# sensor_board_v0_53.net
KiCad netlist of a schematic drawn in EAGLE
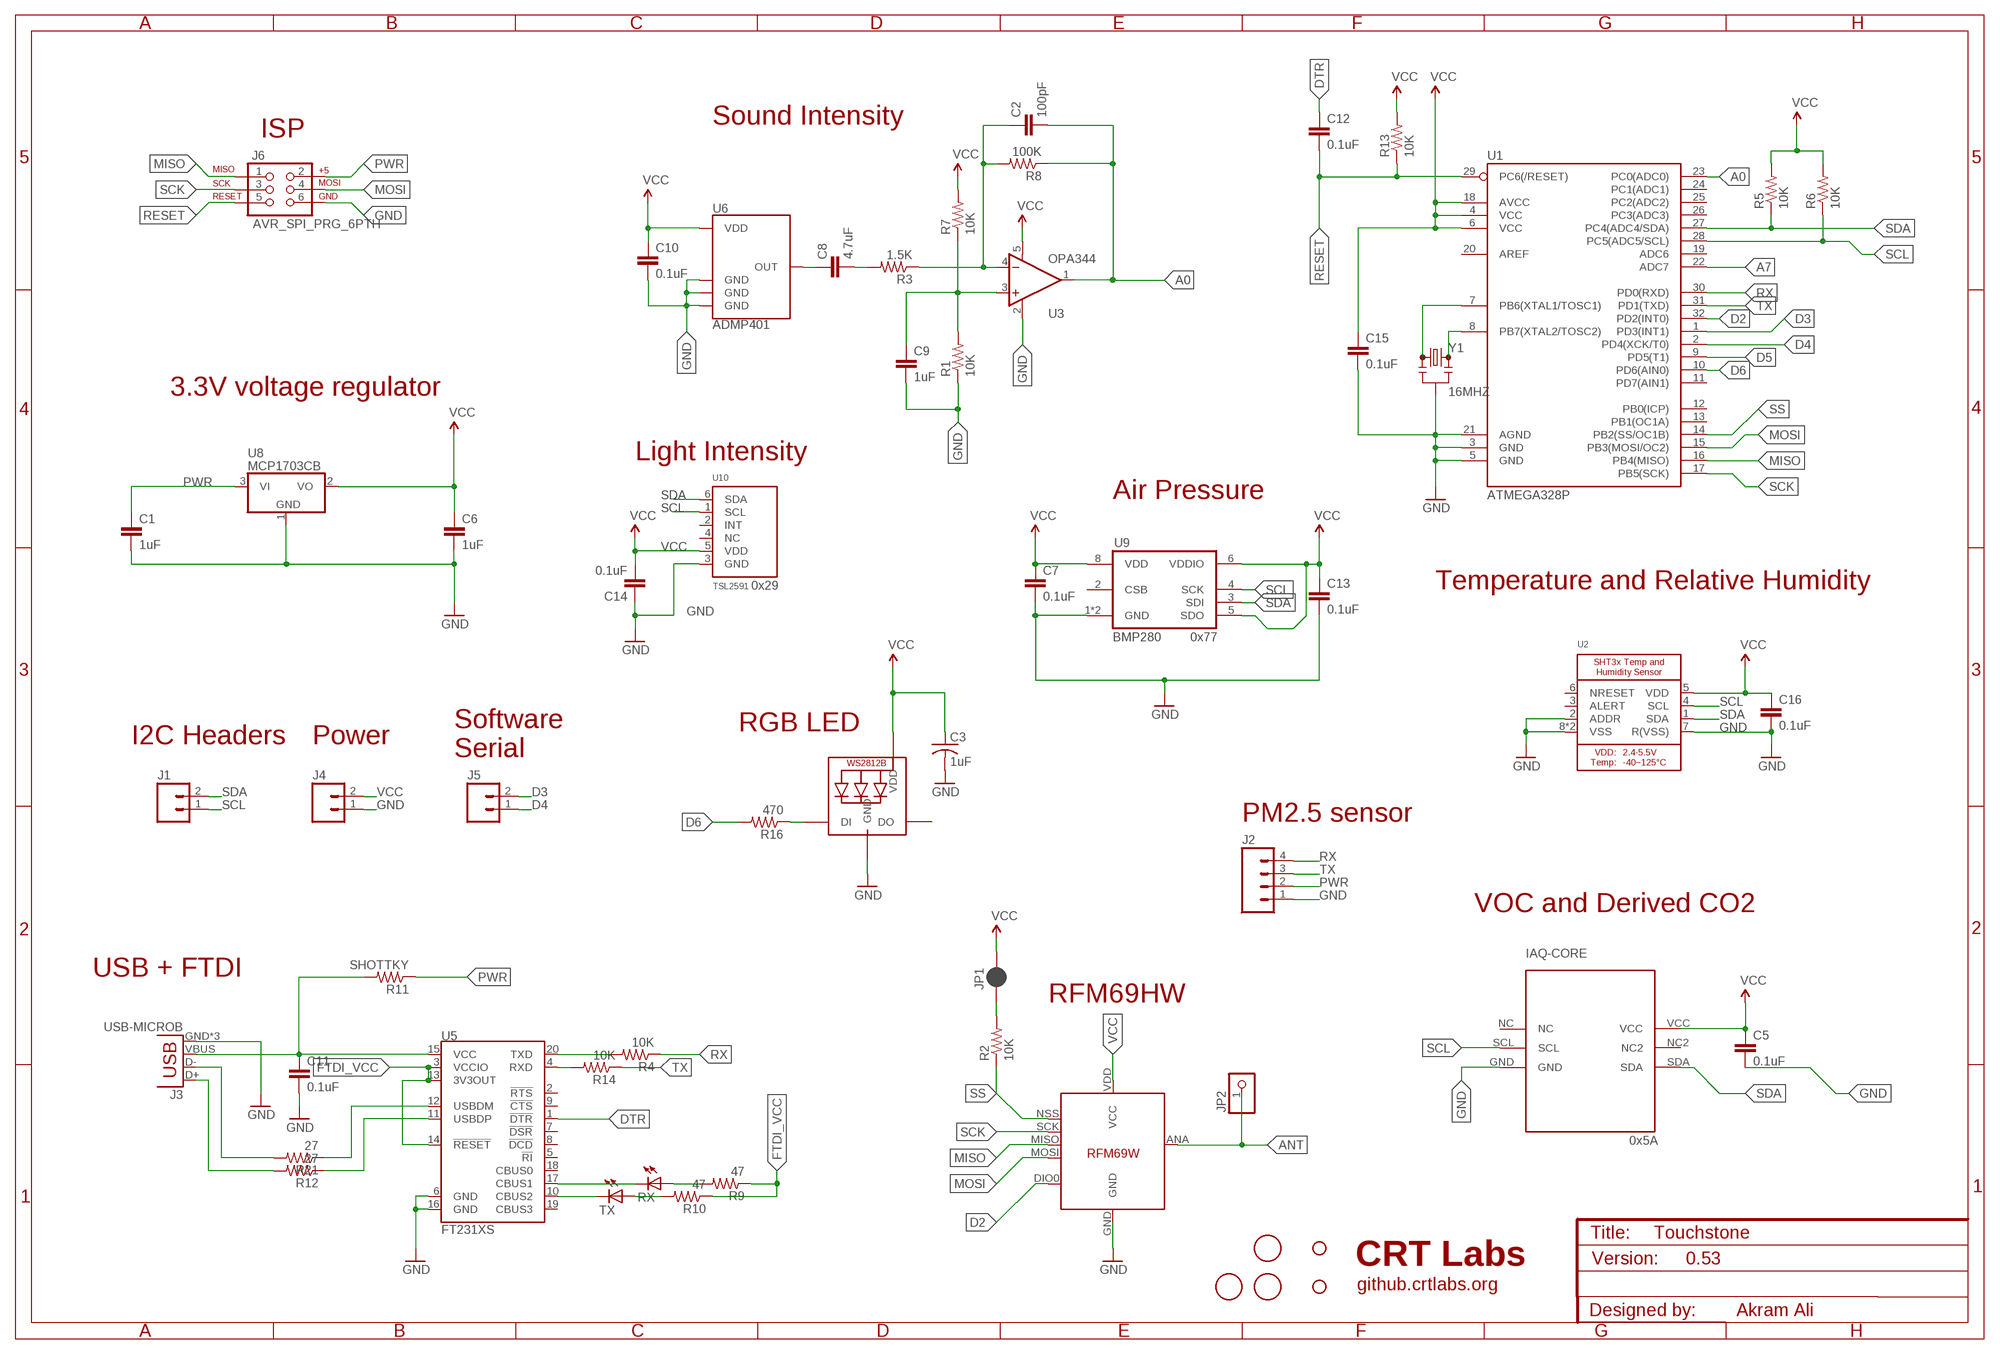
[diagram p0: schematic, sheet 1]

(export (version "E")
  (design (tool "Eeschema 10.0.6"))
  (components
    (comp (ref "C1")
      (value "1uF")
      (footprint "eagle-import:0805")
      (fields (field (name "MPN") "CC0805ZRY5V8BB105"))
      (libsource (lib "eagle-import") (part "CAP0805"))
    )
    (comp (ref "C2")
      (value "100pF")
      (footprint "eagle-import:0805")
      (fields (field (name "MPN") "CC0805JRNPOABN101"))
      (libsource (lib "eagle-import") (part "CAP0805"))
    )
    (comp (ref "C3")
      (value "1uF")
      (footprint "eagle-import:C0603K")
      (fields (field (name "MPN") "CC0805ZRY5V8BB105"))
      (libsource (lib "eagle-import") (part "C-USC0603K"))
    )
    (comp (ref "C5")
      (value "0.1uF")
      (footprint "eagle-import:0805")
      (fields (field (name "MPN") "CC0805KRX7R9BB104"))
      (libsource (lib "eagle-import") (part "SparkFun-Passives_CAP0805"))
    )
    (comp (ref "C6")
      (value "1uF")
      (footprint "eagle-import:0805")
      (fields (field (name "MPN") "CC0805ZRY5V8BB105"))
      (libsource (lib "eagle-import") (part "CAP0805"))
    )
    (comp (ref "C7")
      (value "0.1uF")
      (footprint "eagle-import:0805")
      (fields (field (name "MPN") "CC0805KRX7R9BB104"))
      (libsource (lib "eagle-import") (part "SparkFun-Passives_CAP0805"))
    )
    (comp (ref "C8")
      (value "4.7uF")
      (footprint "eagle-import:0805")
      (fields (field (name "MPN") "CC0805KKX7R6BB475"))
      (libsource (lib "eagle-import") (part "CAP0805"))
    )
    (comp (ref "C9")
      (value "1uF")
      (footprint "eagle-import:0805")
      (fields (field (name "MPN") "CC0805ZRY5V8BB105"))
      (libsource (lib "eagle-import") (part "CAP0805"))
    )
    (comp (ref "C10")
      (value "0.1uF")
      (footprint "eagle-import:0805")
      (fields (field (name "MPN") "CC0805KRX7R9BB104"))
      (libsource (lib "eagle-import") (part "CAP0805"))
    )
    (comp (ref "C11")
      (value "0.1uF")
      (footprint "eagle-import:0805")
      (fields (field (name "MPN") "CC0805KRX7R9BB104"))
      (libsource (lib "eagle-import") (part "CAP0805"))
    )
    (comp (ref "C12")
      (value "0.1uF")
      (footprint "eagle-import:0805")
      (fields (field (name "MPN") "CC0805KRX7R9BB104"))
      (libsource (lib "eagle-import") (part "SparkFun-Passives_CAP0805"))
    )
    (comp (ref "C13")
      (value "0.1uF")
      (footprint "eagle-import:0805")
      (fields (field (name "MPN") "CC0805KRX7R9BB104"))
      (libsource (lib "eagle-import") (part "SparkFun-Passives_CAP0805"))
    )
    (comp (ref "C14")
      (value "0.1uF")
      (footprint "eagle-import:0805")
      (fields (field (name "MPN") "CC0805KRX7R9BB104"))
      (libsource (lib "eagle-import") (part "SparkFun-Passives_CAP0805"))
    )
    (comp (ref "C15")
      (value "0.1uF")
      (footprint "eagle-import:0805")
      (fields (field (name "MPN") "CC0805KRX7R9BB104"))
      (libsource (lib "eagle-import") (part "SparkFun-Passives_CAP0805"))
    )
    (comp (ref "C16")
      (value "0.1uF")
      (footprint "eagle-import:0805")
      (fields (field (name "MPN") "CC0805KRX7R9BB104"))
      (libsource (lib "eagle-import") (part "SparkFun-Passives_CAP0805"))
    )
    (comp (ref "H1")
      (value "STAND-OFF")
      (footprint "eagle-import:STAND-OFF")
      (libsource (lib "eagle-import") (part "STAND-OFF"))
    )
    (comp (ref "H2")
      (value "STAND-OFF")
      (footprint "eagle-import:STAND-OFF")
      (libsource (lib "eagle-import") (part "STAND-OFF"))
    )
    (comp (ref "IAQ-CORE")
      (value "IAQ-CORE")
      (footprint "eagle-import:IAQ-CORE")
      (fields (field (name "MPN") "IAQ-CORE C"))
      (libsource (lib "eagle-import") (part "IAQ-CORE"))
    )
    (comp (ref "J1")
      (value "M02PTH")
      (footprint "eagle-import:1X02")
      (libsource (lib "eagle-import") (part "M02PTH"))
    )
    (comp (ref "J2")
      (value "M04PTH")
      (footprint "eagle-import:1X04")
      (libsource (lib "eagle-import") (part "M04PTH"))
    )
    (comp (ref "J3")
      (value "USB-MICROB")
      (footprint "eagle-import:USB-MICROB")
      (fields (field (name "MPN") "47346-0001"))
      (libsource (lib "eagle-import") (part "USB-MICROB"))
    )
    (comp (ref "J4")
      (value "M02PTH")
      (footprint "eagle-import:1X02")
      (libsource (lib "eagle-import") (part "M02PTH"))
    )
    (comp (ref "J5")
      (value "M02PTH")
      (footprint "eagle-import:1X02")
      (libsource (lib "eagle-import") (part "M02PTH"))
    )
    (comp (ref "J6")
      (value "AVR_SPI_PRG_6PTH")
      (footprint "eagle-import:2X3")
      (libsource (lib "eagle-import") (part "AVR_SPI_PRG_6PTH"))
    )
    (comp (ref "JP1")
      (value "JUMPER-PAD-2-NC_BY_PASTEFULL-BOX-SILK")
      (footprint "eagle-import:PAD-JUMPER-2-NC_BY_PASTE_YES_SILK_FULL_BOX")
      (libsource (lib "eagle-import") (part "JUMPER-PAD-2-NC_BY_PASTEFULL-BOX-SILK"))
    )
    (comp (ref "JP2")
      (value "PINHD-1X1")
      (footprint "eagle-import:1X01")
      (libsource (lib "eagle-import") (part "PINHD-1X1"))
    )
    (comp (ref "LED1")
      (value "WS2812B3535")
      (footprint "eagle-import:LED3535")
      (fields (field (name "MPN") "SK6812 mini"))
      (libsource (lib "eagle-import") (part "WS2812B3535"))
    )
    (comp (ref "R1")
      (value "10K")
      (footprint "eagle-import:0805")
      (fields (field (name "MPN") "RC0805FR-0710KL"))
      (libsource (lib "eagle-import") (part "RESISTOR0805-RES"))
    )
    (comp (ref "R2")
      (value "10K")
      (footprint "eagle-import:0805")
      (fields (field (name "MPN") "RC0805FR-0710KL"))
      (libsource (lib "eagle-import") (part "RESISTOR0805-RES"))
    )
    (comp (ref "R3")
      (value "1.5K")
      (footprint "eagle-import:0805")
      (fields (field (name "MPN") "RC0805FR-071K5L "))
      (libsource (lib "eagle-import") (part "RESISTOR0805-RES"))
    )
    (comp (ref "R4")
      (value "10K")
      (footprint "eagle-import:0805")
      (fields (field (name "MPN") "RC0805FR-0710KL"))
      (libsource (lib "eagle-import") (part "RESISTOR0805-RES"))
    )
    (comp (ref "R5")
      (value "10K")
      (footprint "eagle-import:0805")
      (fields (field (name "MPN") "RC0805FR-0710KL"))
      (libsource (lib "eagle-import") (part "SparkFun-Resistors_RESISTOR0805-RES"))
    )
    (comp (ref "R6")
      (value "10K")
      (footprint "eagle-import:0805")
      (fields (field (name "MPN") "RC0805FR-0710KL"))
      (libsource (lib "eagle-import") (part "SparkFun-Resistors_RESISTOR0805-RES"))
    )
    (comp (ref "R7")
      (value "10K")
      (footprint "eagle-import:0805")
      (fields (field (name "MPN") "RC0805FR-0710KL"))
      (libsource (lib "eagle-import") (part "RESISTOR0805-RES"))
    )
    (comp (ref "R8")
      (value "100K")
      (footprint "eagle-import:0805")
      (fields (field (name "MPN") "RC0805FR-07100KL "))
      (libsource (lib "eagle-import") (part "RESISTOR0805-RES"))
    )
    (comp (ref "R9")
      (value "47")
      (footprint "eagle-import:0805")
      (fields (field (name "MPN") "RC0805FR-0747RL "))
      (libsource (lib "eagle-import") (part "RESISTOR0805-RES"))
    )
    (comp (ref "R10")
      (value "47")
      (footprint "eagle-import:0805")
      (fields (field (name "MPN") "RC0805FR-0747RL "))
      (libsource (lib "eagle-import") (part "RESISTOR0805-RES"))
    )
    (comp (ref "R11")
      (value "SHOTTKY")
      (footprint "eagle-import:0805")
      (fields (field (name "MPN") "SD0805S040S0R5"))
      (libsource (lib "eagle-import") (part "RESISTOR0805-RES"))
    )
    (comp (ref "R12")
      (value "27")
      (footprint "eagle-import:0805")
      (fields (field (name "MPN") "RC0805FR-0727RL "))
      (libsource (lib "eagle-import") (part "RESISTOR0805-RES"))
    )
    (comp (ref "R13")
      (value "10K")
      (footprint "eagle-import:0805")
      (fields (field (name "MPN") "RC0805FR-0710KL"))
      (libsource (lib "eagle-import") (part "RESISTOR0805-RES"))
    )
    (comp (ref "R14")
      (value "10K")
      (footprint "eagle-import:0805")
      (fields (field (name "MPN") "RC0805FR-0710KL"))
      (libsource (lib "eagle-import") (part "RESISTOR0805-RES"))
    )
    (comp (ref "R16")
      (value "470")
      (footprint "eagle-import:R0603")
      (fields (field (name "MPN") "RC0805FR-07470RL "))
      (libsource (lib "eagle-import") (part "R-US_R0603"))
    )
    (comp (ref "R21")
      (value "27")
      (footprint "eagle-import:0805")
      (fields (field (name "MPN") "RC0805FR-0727RL "))
      (libsource (lib "eagle-import") (part "RESISTOR0805-RES"))
    )
    (comp (ref "RX")
      (value "LEDCHIPLED_0805")
      (footprint "eagle-import:CHIPLED_0805")
      (fields (field (name "MPN") "LG R971-KN-1"))
      (libsource (lib "eagle-import") (part "LEDCHIPLED_0805"))
    )
    (comp (ref "TX")
      (value "LEDCHIPLED_0805")
      (footprint "eagle-import:CHIPLED_0805")
      (fields (field (name "MPN") "LG R971-KN-1"))
      (libsource (lib "eagle-import") (part "LEDCHIPLED_0805"))
    )
    (comp (ref "U$1")
      (value "FIDUCIAL")
      (footprint "eagle-import:FIDUCIAL_1MM")
      (libsource (lib "eagle-import") (part "FIDUCIAL"))
    )
    (comp (ref "U$2")
      (value "FIDUCIAL")
      (footprint "eagle-import:FIDUCIAL_1MM")
      (libsource (lib "eagle-import") (part "FIDUCIAL"))
    )
    (comp (ref "U$3")
      (value "FIDUCIAL")
      (footprint "eagle-import:FIDUCIAL_1MM")
      (libsource (lib "eagle-import") (part "FIDUCIAL"))
    )
    (comp (ref "U1")
      (value "ATMEGA328P")
      (footprint "eagle-import:TQFP32-08")
      (fields (field (name "MPN") "ATMEGA328PB-AU"))
      (libsource (lib "eagle-import") (part "ATMEGA328P_TQFP"))
    )
    (comp (ref "U2")
      (value "SHT3X")
      (footprint "eagle-import:SHT3X")
      (fields (field (name "MPN") "SHT35-DIS-B"))
      (libsource (lib "eagle-import") (part "SHT3X"))
    )
    (comp (ref "U3")
      (value "OPA344")
      (footprint "eagle-import:SOT23-5")
      (fields (field (name "MPN") "OPA344NA/3K"))
      (libsource (lib "eagle-import") (part "OPA344"))
    )
    (comp (ref "U4")
      (value "RFM69HW")
      (footprint "eagle-import:LOWPOWERLAB_RFM69W-MINPADS")
      (libsource (lib "eagle-import") (part "LOWPOWERLAB_RFM69"))
    )
    (comp (ref "U5")
      (value "FT231XS")
      (footprint "eagle-import:SSOP20_L")
      (fields (field (name "MPN") "FT231XQ-R"))
      (libsource (lib "eagle-import") (part "FT231XS"))
    )
    (comp (ref "U6")
      (value "ADMP401")
      (footprint "eagle-import:ADMP401")
      (fields (field (name "MPN") "INMP401ACEZ-R7"))
      (libsource (lib "eagle-import") (part "ADMP401"))
    )
    (comp (ref "U8")
      (value "MCP1703CB")
      (footprint "eagle-import:SOT23")
      (fields (field (name "MPN") "MCP1703T-2502E/CB"))
      (libsource (lib "eagle-import") (part "MCP1703CB"))
    )
    (comp (ref "U9")
      (value "BMP280")
      (footprint "eagle-import:BMP280")
      (libsource (lib "eagle-import") (part "BMP280"))
    )
    (comp (ref "U10")
      (value "TSL2591")
      (footprint "eagle-import:DFN6_TAOS")
      (fields (field (name "MPN") "TSL25911FN "))
      (libsource (lib "eagle-import") (part "LIGHT_TSL2591"))
    )
    (comp (ref "Y1")
      (value "16MHZ")
      (footprint "eagle-import:RESONATOR-SMD")
      (fields (field (name "MPN") "CSTCE16M0V53-R0"))
      (libsource (lib "eagle-import") (part "RESONATOR16MHZ"))
    )
  )
  (nets
    (net (code "1") (name "A0") (class "Default")
      (node (ref "C2") (pin "2") (pinfunction "2_2") (pintype "passive"))
      (node (ref "R8") (pin "1") (pinfunction "1_1") (pintype "passive"))
      (node (ref "U1") (pin "23") (pinfunction "PC0(ADC0)_23") (pintype "bidirectional"))
      (node (ref "U3") (pin "1") (pinfunction "OUT_1") (pintype "output"))
    )
    (net (code "2") (name "A7") (class "Default")
      (node (ref "U1") (pin "22") (pinfunction "ADC7_22") (pintype "bidirectional"))
    )
    (net (code "3") (name "ANT") (class "Default")
      (node (ref "JP2") (pin "1") (pinfunction "1_1") (pintype "passive"))
      (node (ref "U4") (pin "ANA") (pinfunction "ANT_ANA") (pintype "passive"))
    )
    (net (code "4") (name "D2") (class "Default")
      (node (ref "U1") (pin "32") (pinfunction "PD2(INT0)_32") (pintype "bidirectional"))
      (node (ref "U4") (pin "DIO0") (pinfunction "DIO0_DIO0") (pintype "open_collector"))
    )
    (net (code "5") (name "D3") (class "Default")
      (node (ref "J5") (pin "2") (pinfunction "2_2") (pintype "passive"))
      (node (ref "U1") (pin "1") (pinfunction "PD3(INT1)_1") (pintype "bidirectional"))
    )
    (net (code "6") (name "D4") (class "Default")
      (node (ref "J5") (pin "1") (pinfunction "1_1") (pintype "passive"))
      (node (ref "U1") (pin "2") (pinfunction "PD4(XCK/T0)_2") (pintype "bidirectional"))
    )
    (net (code "7") (name "D5") (class "Default")
      (node (ref "U1") (pin "9") (pinfunction "PD5(T1)_9") (pintype "bidirectional"))
    )
    (net (code "8") (name "D6") (class "Default")
      (node (ref "R16") (pin "2") (pinfunction "2_2") (pintype "passive"))
      (node (ref "U1") (pin "10") (pinfunction "PD6(AIN0)_10") (pintype "bidirectional"))
    )
    (net (code "9") (name "DTR") (class "Default")
      (node (ref "C12") (pin "1") (pinfunction "1_1") (pintype "passive"))
      (node (ref "U5") (pin "1") (pinfunction "~{DTR}_1") (pintype "bidirectional"))
    )
    (net (code "10") (name "FTDI_VCC") (class "Default")
      (node (ref "R10") (pin "1") (pinfunction "1_1") (pintype "passive"))
      (node (ref "R9") (pin "1") (pinfunction "1_1") (pintype "passive"))
      (node (ref "U5") (pin "13") (pinfunction "3V3OUT_13") (pintype "bidirectional"))
      (node (ref "U5") (pin "14") (pinfunction "~{RESET}_14") (pintype "bidirectional"))
      (node (ref "U5") (pin "3") (pinfunction "VCCIO_3") (pintype "bidirectional"))
    )
    (net (code "11") (name "GND") (class "Default")
      (node (ref "C1") (pin "2") (pinfunction "2_2") (pintype "passive"))
      (node (ref "C10") (pin "2") (pinfunction "2_2") (pintype "passive"))
      (node (ref "C11") (pin "2") (pinfunction "2_2") (pintype "passive"))
      (node (ref "C13") (pin "2") (pinfunction "2_2") (pintype "passive"))
      (node (ref "C14") (pin "1") (pinfunction "1_1") (pintype "passive"))
      (node (ref "C15") (pin "2") (pinfunction "2_2") (pintype "passive"))
      (node (ref "C16") (pin "2") (pinfunction "2_2") (pintype "passive"))
      (node (ref "C3") (pin "2") (pinfunction "2_2") (pintype "passive"))
      (node (ref "C5") (pin "2") (pinfunction "2_2") (pintype "passive"))
      (node (ref "C6") (pin "2") (pinfunction "2_2") (pintype "passive"))
      (node (ref "C7") (pin "2") (pinfunction "2_2") (pintype "passive"))
      (node (ref "C9") (pin "2") (pinfunction "2_2") (pintype "passive"))
      (node (ref "IAQ-CORE") (pin "GND") (pinfunction "GND_GND") (pintype "bidirectional"))
      (node (ref "J2") (pin "1") (pinfunction "1_1") (pintype "passive"))
      (node (ref "J3") (pin "GND") (pinfunction "GND_GND") (pintype "bidirectional"))
      (node (ref "J3") (pin "MT1") (pinfunction "GND_MT1") (pintype "bidirectional"))
      (node (ref "J3") (pin "MT2") (pinfunction "GND_MT2") (pintype "bidirectional"))
      (node (ref "J4") (pin "1") (pinfunction "1_1") (pintype "passive"))
      (node (ref "J6") (pin "6") (pinfunction "6_6") (pintype "passive"))
      (node (ref "LED1") (pin "4") (pinfunction "GND_4") (pintype "power_in"))
      (node (ref "R1") (pin "1") (pinfunction "1_1") (pintype "passive"))
      (node (ref "U1") (pin "21") (pinfunction "AGND_21") (pintype "bidirectional"))
      (node (ref "U1") (pin "3") (pinfunction "GND_3") (pintype "bidirectional"))
      (node (ref "U1") (pin "5") (pinfunction "GND_5") (pintype "bidirectional"))
      (node (ref "U10") (pin "3") (pinfunction "GND_3") (pintype "power_in"))
      (node (ref "U2") (pin "2") (pinfunction "ADDR_2") (pintype "bidirectional"))
      (node (ref "U2") (pin "7") (pinfunction "R(VSS)_7") (pintype "bidirectional"))
      (node (ref "U2") (pin "8") (pinfunction "VSS_8") (pintype "power_in"))
      (node (ref "U2") (pin "THERMAL") (pinfunction "VSS_THERMAL") (pintype "power_in"))
      (node (ref "U3") (pin "2") (pinfunction "V-_2") (pintype "power_in"))
      (node (ref "U4") (pin "GND") (pinfunction "GND_GND") (pintype "power_in"))
      (node (ref "U5") (pin "16") (pinfunction "GND_16") (pintype "bidirectional"))
      (node (ref "U5") (pin "6") (pinfunction "GND_6") (pintype "bidirectional"))
      (node (ref "U6") (pin "2") (pinfunction "GND_2") (pintype "bidirectional"))
      (node (ref "U6") (pin "4") (pinfunction "GND_4") (pintype "bidirectional"))
      (node (ref "U6") (pin "6") (pinfunction "GND_6") (pintype "bidirectional"))
      (node (ref "U8") (pin "1") (pinfunction "GND_1") (pintype "passive"))
      (node (ref "U9") (pin "1") (pinfunction "GND_1") (pintype "power_in"))
      (node (ref "U9") (pin "7") (pinfunction "GND_7") (pintype "power_in"))
      (node (ref "Y1") (pin "2") (pinfunction "2_2") (pintype "passive"))
    )
    (net (code "12") (name "MISO") (class "Default")
      (node (ref "J6") (pin "1") (pinfunction "1_1") (pintype "passive"))
      (node (ref "U1") (pin "16") (pinfunction "PB4(MISO)_16") (pintype "bidirectional"))
      (node (ref "U4") (pin "MISO") (pinfunction "MISO_MISO") (pintype "input"))
    )
    (net (code "13") (name "MOSI") (class "Default")
      (node (ref "J6") (pin "4") (pinfunction "4_4") (pintype "passive"))
      (node (ref "U1") (pin "15") (pinfunction "PB3(MOSI/OC2)_15") (pintype "bidirectional"))
      (node (ref "U4") (pin "MOSI") (pinfunction "MOSI_MOSI") (pintype "output"))
    )
    (net (code "14") (name "Net-(C8-Pad2)") (class "Default")
      (node (ref "C8") (pin "2") (pinfunction "2_2") (pintype "passive"))
      (node (ref "R3") (pin "2") (pinfunction "2_2") (pintype "passive"))
    )
    (net (code "15") (name "Net-(J3-PadD+)") (class "Default")
      (node (ref "J3") (pin "D+") (pinfunction "D+_D+") (pintype "bidirectional"))
      (node (ref "R12") (pin "2") (pinfunction "2_2") (pintype "passive"))
    )
    (net (code "16") (name "Net-(J3-PadD-)") (class "Default")
      (node (ref "J3") (pin "D-") (pinfunction "D-_D-") (pintype "bidirectional"))
      (node (ref "R21") (pin "2") (pinfunction "2_2") (pintype "passive"))
    )
    (net (code "17") (name "Net-(JP1-Pad1)") (class "Default")
      (node (ref "JP1") (pin "1") (pinfunction "1_1") (pintype "passive"))
      (node (ref "R2") (pin "2") (pinfunction "2_2") (pintype "passive"))
    )
    (net (code "18") (name "Net-(LED1-DI)") (class "Default")
      (node (ref "LED1") (pin "1") (pinfunction "DI_1") (pintype "input"))
      (node (ref "R16") (pin "1") (pinfunction "1_1") (pintype "passive"))
    )
    (net (code "19") (name "Net-(R9-Pad2)") (class "Default")
      (node (ref "R9") (pin "2") (pinfunction "2_2") (pintype "passive"))
      (node (ref "RX") (pin "A") (pinfunction "A_A") (pintype "passive"))
    )
    (net (code "20") (name "Net-(R10-Pad2)") (class "Default")
      (node (ref "R10") (pin "2") (pinfunction "2_2") (pintype "passive"))
      (node (ref "TX") (pin "A") (pinfunction "A_A") (pintype "passive"))
    )
    (net (code "21") (name "Net-(U1-PB6(XTAL1{slash}TOSC1))") (class "Default")
      (node (ref "U1") (pin "7") (pinfunction "PB6(XTAL1/TOSC1)_7") (pintype "bidirectional"))
      (node (ref "Y1") (pin "1") (pinfunction "1_1") (pintype "passive"))
    )
    (net (code "22") (name "Net-(U1-PB7(XTAL2{slash}TOSC2))") (class "Default")
      (node (ref "U1") (pin "8") (pinfunction "PB7(XTAL2/TOSC2)_8") (pintype "bidirectional"))
      (node (ref "Y1") (pin "3") (pinfunction "3_3") (pintype "passive"))
    )
    (net (code "23") (name "Net-(U3-+IN)") (class "Default")
      (node (ref "C9") (pin "1") (pinfunction "1_1") (pintype "passive"))
      (node (ref "R1") (pin "2") (pinfunction "2_2") (pintype "passive"))
      (node (ref "R7") (pin "1") (pinfunction "1_1") (pintype "passive"))
      (node (ref "U3") (pin "3") (pinfunction "+IN_3") (pintype "input"))
    )
    (net (code "24") (name "Net-(U3--IN)") (class "Default")
      (node (ref "C2") (pin "1") (pinfunction "1_1") (pintype "passive"))
      (node (ref "R3") (pin "1") (pinfunction "1_1") (pintype "passive"))
      (node (ref "R8") (pin "2") (pinfunction "2_2") (pintype "passive"))
      (node (ref "U3") (pin "4") (pinfunction "-IN_4") (pintype "input"))
    )
    (net (code "25") (name "Net-(U5-CBUS1)") (class "Default")
      (node (ref "RX") (pin "C") (pinfunction "C_C") (pintype "passive"))
      (node (ref "U5") (pin "17") (pinfunction "CBUS1_17") (pintype "bidirectional"))
    )
    (net (code "26") (name "Net-(U5-CBUS2)") (class "Default")
      (node (ref "TX") (pin "C") (pinfunction "C_C") (pintype "passive"))
      (node (ref "U5") (pin "10") (pinfunction "CBUS2_10") (pintype "bidirectional"))
    )
    (net (code "27") (name "Net-(U5-RXD)") (class "Default")
      (node (ref "R14") (pin "2") (pinfunction "2_2") (pintype "passive"))
      (node (ref "U5") (pin "4") (pinfunction "RXD_4") (pintype "bidirectional"))
    )
    (net (code "28") (name "Net-(U5-TXD)") (class "Default")
      (node (ref "R4") (pin "2") (pinfunction "2_2") (pintype "passive"))
      (node (ref "U5") (pin "20") (pinfunction "TXD_20") (pintype "bidirectional"))
    )
    (net (code "29") (name "Net-(U5-USBDM)") (class "Default")
      (node (ref "R21") (pin "1") (pinfunction "1_1") (pintype "passive"))
      (node (ref "U5") (pin "12") (pinfunction "USBDM_12") (pintype "bidirectional"))
    )
    (net (code "30") (name "Net-(U5-USBDP)") (class "Default")
      (node (ref "R12") (pin "1") (pinfunction "1_1") (pintype "passive"))
      (node (ref "U5") (pin "11") (pinfunction "USBDP_11") (pintype "bidirectional"))
    )
    (net (code "31") (name "Net-(U5-VCC)") (class "Default")
      (node (ref "C11") (pin "1") (pinfunction "1_1") (pintype "passive"))
      (node (ref "J3") (pin "VBUS") (pinfunction "VBUS_VBUS") (pintype "bidirectional"))
      (node (ref "R11") (pin "2") (pinfunction "2_2") (pintype "passive"))
      (node (ref "U5") (pin "15") (pinfunction "VCC_15") (pintype "bidirectional"))
    )
    (net (code "32") (name "Net-(U6-OUT)") (class "Default")
      (node (ref "C8") (pin "1") (pinfunction "1_1") (pintype "passive"))
      (node (ref "U6") (pin "1") (pinfunction "OUT_1") (pintype "bidirectional"))
    )
    (net (code "33") (name "PWR") (class "Default")
      (node (ref "C1") (pin "1") (pinfunction "1_1") (pintype "passive"))
      (node (ref "J2") (pin "2") (pinfunction "2_2") (pintype "passive"))
      (node (ref "J6") (pin "2") (pinfunction "2_2") (pintype "passive"))
      (node (ref "R11") (pin "1") (pinfunction "1_1") (pintype "passive"))
      (node (ref "U8") (pin "3") (pinfunction "VI_3") (pintype "input"))
    )
    (net (code "34") (name "RESET") (class "Default")
      (node (ref "C12") (pin "2") (pinfunction "2_2") (pintype "passive"))
      (node (ref "J6") (pin "5") (pinfunction "5_5") (pintype "passive"))
      (node (ref "R13") (pin "1") (pinfunction "1_1") (pintype "passive"))
      (node (ref "U1") (pin "29") (pinfunction "PC6(/RESET)_29") (pintype "bidirectional"))
    )
    (net (code "35") (name "RX") (class "Default")
      (node (ref "J2") (pin "4") (pinfunction "4_4") (pintype "passive"))
      (node (ref "R4") (pin "1") (pinfunction "1_1") (pintype "passive"))
      (node (ref "U1") (pin "30") (pinfunction "PD0(RXD)_30") (pintype "bidirectional"))
    )
    (net (code "36") (name "SCK") (class "Default")
      (node (ref "J6") (pin "3") (pinfunction "3_3") (pintype "passive"))
      (node (ref "U1") (pin "17") (pinfunction "PB5(SCK)_17") (pintype "bidirectional"))
      (node (ref "U4") (pin "SCK") (pinfunction "SCK_SCK") (pintype "input"))
    )
    (net (code "37") (name "SCL") (class "Default")
      (node (ref "IAQ-CORE") (pin "SCL") (pinfunction "SCL_SCL") (pintype "bidirectional"))
      (node (ref "J1") (pin "1") (pinfunction "1_1") (pintype "passive"))
      (node (ref "R6") (pin "1") (pinfunction "1_1") (pintype "passive"))
      (node (ref "U1") (pin "28") (pinfunction "PC5(ADC5/SCL)_28") (pintype "bidirectional"))
      (node (ref "U10") (pin "1") (pinfunction "SCL_1") (pintype "bidirectional"))
      (node (ref "U2") (pin "4") (pinfunction "SCL_4") (pintype "bidirectional"))
      (node (ref "U9") (pin "4") (pinfunction "SCK_4") (pintype "bidirectional"))
    )
    (net (code "38") (name "SDA") (class "Default")
      (node (ref "IAQ-CORE") (pin "SDA") (pinfunction "SDA_SDA") (pintype "bidirectional"))
      (node (ref "J1") (pin "2") (pinfunction "2_2") (pintype "passive"))
      (node (ref "R5") (pin "1") (pinfunction "1_1") (pintype "passive"))
      (node (ref "U1") (pin "27") (pinfunction "PC4(ADC4/SDA)_27") (pintype "bidirectional"))
      (node (ref "U10") (pin "6") (pinfunction "SDA_6") (pintype "bidirectional"))
      (node (ref "U2") (pin "1") (pinfunction "SDA_1") (pintype "bidirectional"))
      (node (ref "U9") (pin "3") (pinfunction "SDI_3") (pintype "bidirectional"))
    )
    (net (code "39") (name "SS") (class "Default")
      (node (ref "R2") (pin "1") (pinfunction "1_1") (pintype "passive"))
      (node (ref "U1") (pin "14") (pinfunction "PB2(SS/OC1B)_14") (pintype "bidirectional"))
      (node (ref "U4") (pin "NSS") (pinfunction "SEL_NSS") (pintype "input"))
    )
    (net (code "40") (name "TX") (class "Default")
      (node (ref "J2") (pin "3") (pinfunction "3_3") (pintype "passive"))
      (node (ref "R14") (pin "1") (pinfunction "1_1") (pintype "passive"))
      (node (ref "U1") (pin "31") (pinfunction "PD1(TXD)_31") (pintype "bidirectional"))
    )
    (net (code "41") (name "VCC") (class "Default")
      (node (ref "C10") (pin "1") (pinfunction "1_1") (pintype "passive"))
      (node (ref "C13") (pin "1") (pinfunction "1_1") (pintype "passive"))
      (node (ref "C14") (pin "2") (pinfunction "2_2") (pintype "passive"))
      (node (ref "C15") (pin "1") (pinfunction "1_1") (pintype "passive"))
      (node (ref "C16") (pin "1") (pinfunction "1_1") (pintype "passive"))
      (node (ref "C3") (pin "1") (pinfunction "1_1") (pintype "passive"))
      (node (ref "C5") (pin "1") (pinfunction "1_1") (pintype "passive"))
      (node (ref "C6") (pin "1") (pinfunction "1_1") (pintype "passive"))
      (node (ref "C7") (pin "1") (pinfunction "1_1") (pintype "passive"))
      (node (ref "IAQ-CORE") (pin "VCC") (pinfunction "VCC_VCC") (pintype "bidirectional"))
      (node (ref "J4") (pin "2") (pinfunction "2_2") (pintype "passive"))
      (node (ref "JP1") (pin "2") (pinfunction "2_2") (pintype "passive"))
      (node (ref "LED1") (pin "2") (pinfunction "VDD_2") (pintype "power_in"))
      (node (ref "R13") (pin "2") (pinfunction "2_2") (pintype "passive"))
      (node (ref "R5") (pin "2") (pinfunction "2_2") (pintype "passive"))
      (node (ref "R6") (pin "2") (pinfunction "2_2") (pintype "passive"))
      (node (ref "R7") (pin "2") (pinfunction "2_2") (pintype "passive"))
      (node (ref "U1") (pin "18") (pinfunction "AVCC_18") (pintype "bidirectional"))
      (node (ref "U1") (pin "4") (pinfunction "VCC_4") (pintype "bidirectional"))
      (node (ref "U1") (pin "6") (pinfunction "VCC_6") (pintype "bidirectional"))
      (node (ref "U10") (pin "5") (pinfunction "VDD_5") (pintype "power_in"))
      (node (ref "U2") (pin "5") (pinfunction "VDD_5") (pintype "power_in"))
      (node (ref "U3") (pin "5") (pinfunction "V+_5") (pintype "power_in"))
      (node (ref "U4") (pin "VDD") (pinfunction "VCC_VDD") (pintype "power_in"))
      (node (ref "U6") (pin "5") (pinfunction "VDD_5") (pintype "bidirectional"))
      (node (ref "U8") (pin "2") (pinfunction "VO_2") (pintype "passive"))
      (node (ref "U9") (pin "5") (pinfunction "SDO_5") (pintype "input"))
      (node (ref "U9") (pin "6") (pinfunction "VDDIO_6") (pintype "power_in"))
      (node (ref "U9") (pin "8") (pinfunction "VDD_8") (pintype "power_in"))
    )
    (net (code "42") (name "unconnected-(IAQ-CORE-PadNC)") (class "Default")
      (node (ref "IAQ-CORE") (pin "NC") (pinfunction "NC_NC") (pintype "bidirectional"))
    )
    (net (code "43") (name "unconnected-(IAQ-CORE-PadNC2)") (class "Default")
      (node (ref "IAQ-CORE") (pin "NC2") (pinfunction "NC2_NC2") (pintype "bidirectional"))
    )
    (net (code "44") (name "unconnected-(LED1-DO-Pad3)") (class "Default")
      (node (ref "LED1") (pin "3") (pinfunction "DO_3") (pintype "output"))
    )
    (net (code "45") (name "unconnected-(U1-ADC6-Pad19)") (class "Default")
      (node (ref "U1") (pin "19") (pinfunction "ADC6_19") (pintype "bidirectional"))
    )
    (net (code "46") (name "unconnected-(U1-AREF-Pad20)") (class "Default")
      (node (ref "U1") (pin "20") (pinfunction "AREF_20") (pintype "bidirectional"))
    )
    (net (code "47") (name "unconnected-(U1-PB0(ICP)-Pad12)") (class "Default")
      (node (ref "U1") (pin "12") (pinfunction "PB0(ICP)_12") (pintype "bidirectional"))
    )
    (net (code "48") (name "unconnected-(U1-PB1(OC1A)-Pad13)") (class "Default")
      (node (ref "U1") (pin "13") (pinfunction "PB1(OC1A)_13") (pintype "bidirectional"))
    )
    (net (code "49") (name "unconnected-(U1-PC1(ADC1)-Pad24)") (class "Default")
      (node (ref "U1") (pin "24") (pinfunction "PC1(ADC1)_24") (pintype "bidirectional"))
    )
    (net (code "50") (name "unconnected-(U1-PC2(ADC2)-Pad25)") (class "Default")
      (node (ref "U1") (pin "25") (pinfunction "PC2(ADC2)_25") (pintype "bidirectional"))
    )
    (net (code "51") (name "unconnected-(U1-PC3(ADC3)-Pad26)") (class "Default")
      (node (ref "U1") (pin "26") (pinfunction "PC3(ADC3)_26") (pintype "bidirectional"))
    )
    (net (code "52") (name "unconnected-(U1-PD7(AIN1)-Pad11)") (class "Default")
      (node (ref "U1") (pin "11") (pinfunction "PD7(AIN1)_11") (pintype "bidirectional"))
    )
    (net (code "53") (name "unconnected-(U2-ALERT-Pad3)") (class "Default")
      (node (ref "U2") (pin "3") (pinfunction "ALERT_3") (pintype "bidirectional"))
    )
    (net (code "54") (name "unconnected-(U2-NRESET-Pad6)") (class "Default")
      (node (ref "U2") (pin "6") (pinfunction "NRESET_6") (pintype "bidirectional"))
    )
    (net (code "55") (name "unconnected-(U5-CBUS0-Pad18)") (class "Default")
      (node (ref "U5") (pin "18") (pinfunction "CBUS0_18") (pintype "bidirectional"))
    )
    (net (code "56") (name "unconnected-(U5-CBUS3-Pad19)") (class "Default")
      (node (ref "U5") (pin "19") (pinfunction "CBUS3_19") (pintype "bidirectional"))
    )
    (net (code "57") (name "unconnected-(U5-~{CTS}-Pad9)") (class "Default")
      (node (ref "U5") (pin "9") (pinfunction "~{CTS}_9") (pintype "bidirectional"))
    )
    (net (code "58") (name "unconnected-(U5-~{DCD}-Pad8)") (class "Default")
      (node (ref "U5") (pin "8") (pinfunction "~{DCD}_8") (pintype "bidirectional"))
    )
    (net (code "59") (name "unconnected-(U5-~{DSR}-Pad7)") (class "Default")
      (node (ref "U5") (pin "7") (pinfunction "~{DSR}_7") (pintype "bidirectional"))
    )
    (net (code "60") (name "unconnected-(U5-~{RI}-Pad5)") (class "Default")
      (node (ref "U5") (pin "5") (pinfunction "~{RI}_5") (pintype "bidirectional"))
    )
    (net (code "61") (name "unconnected-(U5-~{RTS}-Pad2)") (class "Default")
      (node (ref "U5") (pin "2") (pinfunction "~{RTS}_2") (pintype "bidirectional"))
    )
    (net (code "62") (name "unconnected-(U9-CSB-Pad2)") (class "Default")
      (node (ref "U9") (pin "2") (pinfunction "CSB_2") (pintype "input"))
    )
    (net (code "63") (name "unconnected-(U10-INT-Pad2)") (class "Default")
      (node (ref "U10") (pin "2") (pinfunction "INT_2") (pintype "output"))
    )
    (net (code "64") (name "unconnected-(U10-NC-Pad4)") (class "Default")
      (node (ref "U10") (pin "4") (pinfunction "NC_4") (pintype "no_connect"))
    )
  )
)
